# Sheet1.net
KiCad netlist of a schematic drawn in Altium Designer
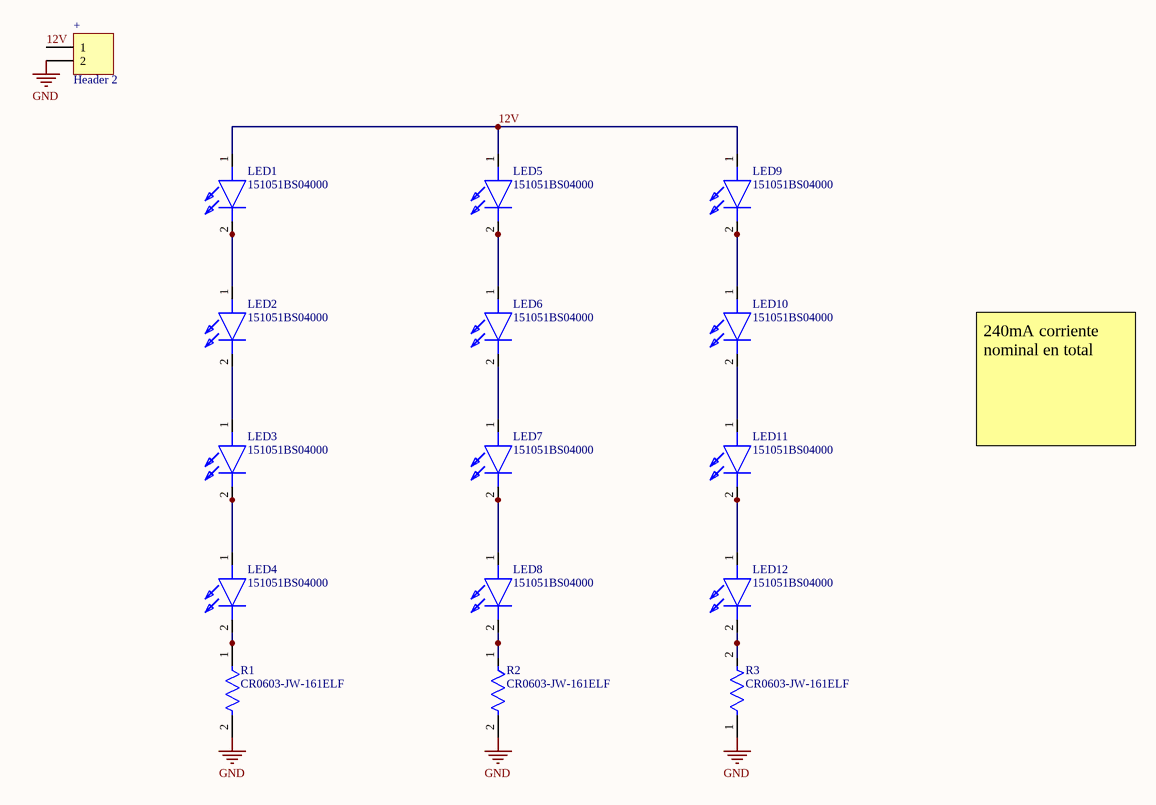
[diagram p0: Sheet1.SchDoc]

(export (version "E")
  (design (tool "Eeschema 10.0.6"))
  (components
    (comp (ref "+")
      (value "Header 2")
      (footprint "HDR1X2")
      (description "Header, 2-Pin")
      (fields (field (name "PUBLISHER") "Altium Limited"))
      (libsource (lib "Miscellaneous Connectors") (part "Header 2"))
    )
    (comp (ref "LED1")
      (value "151051BS04000")
      (footprint "SamacSys:151051BS04000")
      (description "LED")
      (fields (field (name "MOUSER PART NUMBER") "710-151051BS04000"))
      (libsource (lib "*") (part "151051BS04000"))
    )
    (comp (ref "LED2")
      (value "151051BS04000")
      (footprint "SamacSys:151051BS04000")
      (description "LED")
      (fields (field (name "MOUSER PART NUMBER") "710-151051BS04000"))
      (libsource (lib "*") (part "151051BS04000"))
    )
    (comp (ref "LED3")
      (value "151051BS04000")
      (footprint "SamacSys:151051BS04000")
      (description "LED")
      (fields (field (name "MOUSER PART NUMBER") "710-151051BS04000"))
      (libsource (lib "*") (part "151051BS04000"))
    )
    (comp (ref "LED4")
      (value "151051BS04000")
      (footprint "SamacSys:151051BS04000")
      (description "LED")
      (fields (field (name "MOUSER PART NUMBER") "710-151051BS04000"))
      (libsource (lib "*") (part "151051BS04000"))
    )
    (comp (ref "LED5")
      (value "151051BS04000")
      (footprint "SamacSys:151051BS04000")
      (description "LED")
      (fields (field (name "MOUSER PART NUMBER") "710-151051BS04000"))
      (libsource (lib "*") (part "151051BS04000"))
    )
    (comp (ref "LED6")
      (value "151051BS04000")
      (footprint "SamacSys:151051BS04000")
      (description "LED")
      (fields (field (name "MOUSER PART NUMBER") "710-151051BS04000"))
      (libsource (lib "*") (part "151051BS04000"))
    )
    (comp (ref "LED7")
      (value "151051BS04000")
      (footprint "SamacSys:151051BS04000")
      (description "LED")
      (fields (field (name "MOUSER PART NUMBER") "710-151051BS04000"))
      (libsource (lib "*") (part "151051BS04000"))
    )
    (comp (ref "LED8")
      (value "151051BS04000")
      (footprint "SamacSys:151051BS04000")
      (description "LED")
      (fields (field (name "MOUSER PART NUMBER") "710-151051BS04000"))
      (libsource (lib "*") (part "151051BS04000"))
    )
    (comp (ref "LED9")
      (value "151051BS04000")
      (footprint "SamacSys:151051BS04000")
      (description "LED")
      (fields (field (name "MOUSER PART NUMBER") "710-151051BS04000"))
      (libsource (lib "*") (part "151051BS04000"))
    )
    (comp (ref "LED10")
      (value "151051BS04000")
      (footprint "SamacSys:151051BS04000")
      (description "LED")
      (fields (field (name "MOUSER PART NUMBER") "710-151051BS04000"))
      (libsource (lib "*") (part "151051BS04000"))
    )
    (comp (ref "LED11")
      (value "151051BS04000")
      (footprint "SamacSys:151051BS04000")
      (description "LED")
      (fields (field (name "MOUSER PART NUMBER") "710-151051BS04000"))
      (libsource (lib "*") (part "151051BS04000"))
    )
    (comp (ref "LED12")
      (value "151051BS04000")
      (footprint "SamacSys:151051BS04000")
      (description "LED")
      (fields (field (name "MOUSER PART NUMBER") "710-151051BS04000"))
      (libsource (lib "*") (part "151051BS04000"))
    )
    (comp (ref "R1")
      (value "CR0603-JW-161ELF")
      (footprint "FP-CR0603-IPC_B")
      (description "Thick Film Chip Resistors 0603 160Ω 0.1W 5% 200ppm/°C")
      (fields (field (name "TOLERANCE") "5%"))
      (libsource (lib "Altium Content Vault") (part "1029c3af85768c4190bb7ad29bc67b5"))
    )
    (comp (ref "R2")
      (value "CR0603-JW-161ELF")
      (footprint "FP-CR0603-IPC_B")
      (description "Thick Film Chip Resistors 0603 160Ω 0.1W 5% 200ppm/°C")
      (fields (field (name "TOLERANCE") "5%"))
      (libsource (lib "Altium Content Vault") (part "1029c3af85768c4190bb7ad29bc67b5"))
    )
    (comp (ref "R3")
      (value "CR0603-JW-161ELF")
      (footprint "FP-CR0603-IPC_B")
      (description "Thick Film Chip Resistors 0603 160Ω 0.1W 5% 200ppm/°C")
      (fields (field (name "TOLERANCE") "5%"))
      (libsource (lib "Altium Content Vault") (part "1029c3af85768c4190bb7ad29bc67b5"))
    )
  )
  (nets
    (net (code "1") (name "/12V") (class "Default")
      (node (ref "+") (pin "1") (pinfunction "1_1") (pintype "passive"))
      (node (ref "LED1") (pin "1") (pinfunction "A_1") (pintype "passive"))
      (node (ref "LED5") (pin "1") (pinfunction "A_1") (pintype "passive"))
      (node (ref "LED9") (pin "1") (pinfunction "A_1") (pintype "passive"))
    )
    (net (code "2") (name "GND") (class "Default")
      (node (ref "+") (pin "2") (pinfunction "2_2") (pintype "passive"))
      (node (ref "R1") (pin "2") (pinfunction "2_2") (pintype "passive"))
      (node (ref "R2") (pin "2") (pinfunction "2_2") (pintype "passive"))
      (node (ref "R3") (pin "1") (pinfunction "1_1") (pintype "passive"))
    )
    (net (code "3") (name "Net-(LED1-K)") (class "Default")
      (node (ref "LED1") (pin "2") (pinfunction "K_2") (pintype "passive"))
      (node (ref "LED2") (pin "1") (pinfunction "A_1") (pintype "passive"))
    )
    (net (code "4") (name "Net-(LED2-K)") (class "Default")
      (node (ref "LED2") (pin "2") (pinfunction "K_2") (pintype "passive"))
      (node (ref "LED3") (pin "1") (pinfunction "A_1") (pintype "passive"))
    )
    (net (code "5") (name "Net-(LED3-K)") (class "Default")
      (node (ref "LED3") (pin "2") (pinfunction "K_2") (pintype "passive"))
      (node (ref "LED4") (pin "1") (pinfunction "A_1") (pintype "passive"))
    )
    (net (code "6") (name "Net-(LED4-K)") (class "Default")
      (node (ref "LED4") (pin "2") (pinfunction "K_2") (pintype "passive"))
      (node (ref "R1") (pin "1") (pinfunction "1_1") (pintype "passive"))
    )
    (net (code "7") (name "Net-(LED5-K)") (class "Default")
      (node (ref "LED5") (pin "2") (pinfunction "K_2") (pintype "passive"))
      (node (ref "LED6") (pin "1") (pinfunction "A_1") (pintype "passive"))
    )
    (net (code "8") (name "Net-(LED6-K)") (class "Default")
      (node (ref "LED6") (pin "2") (pinfunction "K_2") (pintype "passive"))
      (node (ref "LED7") (pin "1") (pinfunction "A_1") (pintype "passive"))
    )
    (net (code "9") (name "Net-(LED7-K)") (class "Default")
      (node (ref "LED7") (pin "2") (pinfunction "K_2") (pintype "passive"))
      (node (ref "LED8") (pin "1") (pinfunction "A_1") (pintype "passive"))
    )
    (net (code "10") (name "Net-(LED8-K)") (class "Default")
      (node (ref "LED8") (pin "2") (pinfunction "K_2") (pintype "passive"))
      (node (ref "R2") (pin "1") (pinfunction "1_1") (pintype "passive"))
    )
    (net (code "11") (name "Net-(LED10-A)") (class "Default")
      (node (ref "LED10") (pin "1") (pinfunction "A_1") (pintype "passive"))
      (node (ref "LED9") (pin "2") (pinfunction "K_2") (pintype "passive"))
    )
    (net (code "12") (name "Net-(LED10-K)") (class "Default")
      (node (ref "LED10") (pin "2") (pinfunction "K_2") (pintype "passive"))
      (node (ref "LED11") (pin "1") (pinfunction "A_1") (pintype "passive"))
    )
    (net (code "13") (name "Net-(LED11-K)") (class "Default")
      (node (ref "LED11") (pin "2") (pinfunction "K_2") (pintype "passive"))
      (node (ref "LED12") (pin "1") (pinfunction "A_1") (pintype "passive"))
    )
    (net (code "14") (name "Net-(LED12-K)") (class "Default")
      (node (ref "LED12") (pin "2") (pinfunction "K_2") (pintype "passive"))
      (node (ref "R3") (pin "2") (pinfunction "2_2") (pintype "passive"))
    )
  )
)
